# Alignment.net
KiCad netlist of a schematic drawn in EAGLE
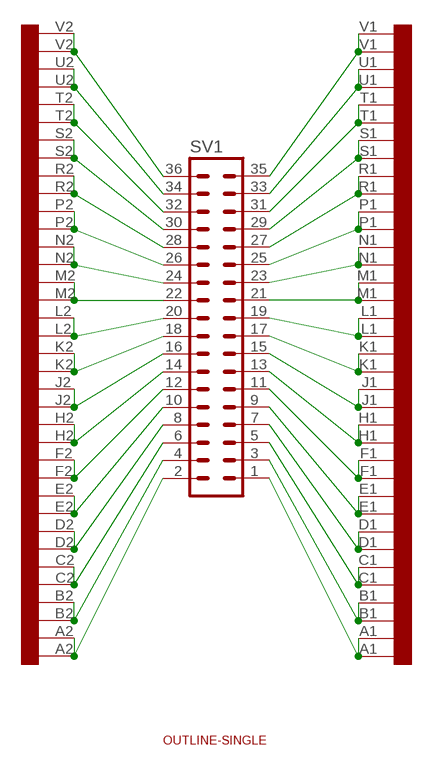
[diagram p0: schematic, sheet 1]

(export (version "E")
  (design (tool "Eeschema 10.0.6"))
  (components
    (comp (ref "EDGE")
      (value "EDGE-2ECONO")
      (footprint "eagle-import:ECONOSINGLE")
      (libsource (lib "eagle-import") (part "EDGE-2ECONO"))
    )
    (comp (ref "SV1")
      (value "MA18-2")
      (footprint "eagle-import:MA18-2")
      (libsource (lib "eagle-import") (part "MA18-2"))
    )
    (comp (ref "U$1")
      (value "EDGE-2CONNECTOR")
      (footprint "eagle-import:EDGE-CON2")
      (libsource (lib "eagle-import") (part "EDGE-2CONNECTOR"))
    )
    (comp (ref "U$3")
      (value "OUTLINE-SINGLE")
      (footprint "eagle-import:SINGLE")
      (libsource (lib "eagle-import") (part "OUTLINE-SINGLE"))
    )
  )
  (nets
    (net (code "1") (name "Net-(EDGEA-1)") (class "Default")
      (node (ref "EDGE") (pin "A1") (pinfunction "1_A1") (pintype "bidirectional"))
      (node (ref "SV1") (pin "1") (pinfunction "1_1") (pintype "passive"))
      (node (ref "U$1") (pin "A1") (pinfunction "1_A1") (pintype "bidirectional"))
    )
    (net (code "2") (name "Net-(EDGEAA-1)") (class "Default")
      (node (ref "EDGE") (pin "R1") (pinfunction "1_R1") (pintype "bidirectional"))
      (node (ref "SV1") (pin "27") (pinfunction "27_27") (pintype "passive"))
      (node (ref "U$1") (pin "R1") (pinfunction "1_R1") (pintype "bidirectional"))
    )
    (net (code "3") (name "Net-(EDGEAB-1)") (class "Default")
      (node (ref "EDGE") (pin "R2") (pinfunction "1_R2") (pintype "bidirectional"))
      (node (ref "SV1") (pin "28") (pinfunction "28_28") (pintype "passive"))
      (node (ref "U$1") (pin "R2") (pinfunction "1_R2") (pintype "bidirectional"))
    )
    (net (code "4") (name "Net-(EDGEAC-1)") (class "Default")
      (node (ref "EDGE") (pin "S1") (pinfunction "1_S1") (pintype "bidirectional"))
      (node (ref "SV1") (pin "29") (pinfunction "29_29") (pintype "passive"))
      (node (ref "U$1") (pin "S1") (pinfunction "1_S1") (pintype "bidirectional"))
    )
    (net (code "5") (name "Net-(EDGEAD-1)") (class "Default")
      (node (ref "EDGE") (pin "S2") (pinfunction "1_S2") (pintype "bidirectional"))
      (node (ref "SV1") (pin "30") (pinfunction "30_30") (pintype "passive"))
      (node (ref "U$1") (pin "S2") (pinfunction "1_S2") (pintype "bidirectional"))
    )
    (net (code "6") (name "Net-(EDGEAE-1)") (class "Default")
      (node (ref "EDGE") (pin "T1") (pinfunction "1_T1") (pintype "bidirectional"))
      (node (ref "SV1") (pin "31") (pinfunction "31_31") (pintype "passive"))
      (node (ref "U$1") (pin "T1") (pinfunction "1_T1") (pintype "bidirectional"))
    )
    (net (code "7") (name "Net-(EDGEAF-1)") (class "Default")
      (node (ref "EDGE") (pin "T2") (pinfunction "1_T2") (pintype "bidirectional"))
      (node (ref "SV1") (pin "32") (pinfunction "32_32") (pintype "passive"))
      (node (ref "U$1") (pin "T2") (pinfunction "1_T2") (pintype "bidirectional"))
    )
    (net (code "8") (name "Net-(EDGEAG-1)") (class "Default")
      (node (ref "EDGE") (pin "U1") (pinfunction "1_U1") (pintype "bidirectional"))
      (node (ref "SV1") (pin "33") (pinfunction "33_33") (pintype "passive"))
      (node (ref "U$1") (pin "U1") (pinfunction "1_U1") (pintype "bidirectional"))
    )
    (net (code "9") (name "Net-(EDGEAH-1)") (class "Default")
      (node (ref "EDGE") (pin "U2") (pinfunction "1_U2") (pintype "bidirectional"))
      (node (ref "SV1") (pin "34") (pinfunction "34_34") (pintype "passive"))
      (node (ref "U$1") (pin "U2") (pinfunction "1_U2") (pintype "bidirectional"))
    )
    (net (code "10") (name "Net-(EDGEAI-1)") (class "Default")
      (node (ref "EDGE") (pin "V1") (pinfunction "1_V1") (pintype "bidirectional"))
      (node (ref "SV1") (pin "35") (pinfunction "35_35") (pintype "passive"))
      (node (ref "U$1") (pin "V1") (pinfunction "1_V1") (pintype "bidirectional"))
    )
    (net (code "11") (name "Net-(EDGEAJ-1)") (class "Default")
      (node (ref "EDGE") (pin "V2") (pinfunction "1_V2") (pintype "bidirectional"))
      (node (ref "SV1") (pin "36") (pinfunction "36_36") (pintype "passive"))
      (node (ref "U$1") (pin "V2") (pinfunction "1_V2") (pintype "bidirectional"))
    )
    (net (code "12") (name "Net-(EDGEB-1)") (class "Default")
      (node (ref "EDGE") (pin "A2") (pinfunction "1_A2") (pintype "bidirectional"))
      (node (ref "SV1") (pin "2") (pinfunction "2_2") (pintype "passive"))
      (node (ref "U$1") (pin "A2") (pinfunction "1_A2") (pintype "bidirectional"))
    )
    (net (code "13") (name "Net-(EDGEC-1)") (class "Default")
      (node (ref "EDGE") (pin "B1") (pinfunction "1_B1") (pintype "bidirectional"))
      (node (ref "SV1") (pin "3") (pinfunction "3_3") (pintype "passive"))
      (node (ref "U$1") (pin "B1") (pinfunction "1_B1") (pintype "bidirectional"))
    )
    (net (code "14") (name "Net-(EDGED-1)") (class "Default")
      (node (ref "EDGE") (pin "B2") (pinfunction "1_B2") (pintype "bidirectional"))
      (node (ref "SV1") (pin "4") (pinfunction "4_4") (pintype "passive"))
      (node (ref "U$1") (pin "B2") (pinfunction "1_B2") (pintype "bidirectional"))
    )
    (net (code "15") (name "Net-(EDGEE-1)") (class "Default")
      (node (ref "EDGE") (pin "C1") (pinfunction "1_C1") (pintype "bidirectional"))
      (node (ref "SV1") (pin "5") (pinfunction "5_5") (pintype "passive"))
      (node (ref "U$1") (pin "C1") (pinfunction "1_C1") (pintype "bidirectional"))
    )
    (net (code "16") (name "Net-(EDGEF-1)") (class "Default")
      (node (ref "EDGE") (pin "C2") (pinfunction "1_C2") (pintype "bidirectional"))
      (node (ref "SV1") (pin "6") (pinfunction "6_6") (pintype "passive"))
      (node (ref "U$1") (pin "C2") (pinfunction "1_C2") (pintype "bidirectional"))
    )
    (net (code "17") (name "Net-(EDGEG-1)") (class "Default")
      (node (ref "EDGE") (pin "D1") (pinfunction "1_D1") (pintype "bidirectional"))
      (node (ref "SV1") (pin "7") (pinfunction "7_7") (pintype "passive"))
      (node (ref "U$1") (pin "D1") (pinfunction "1_D1") (pintype "bidirectional"))
    )
    (net (code "18") (name "Net-(EDGEH-1)") (class "Default")
      (node (ref "EDGE") (pin "D2") (pinfunction "1_D2") (pintype "bidirectional"))
      (node (ref "SV1") (pin "8") (pinfunction "8_8") (pintype "passive"))
      (node (ref "U$1") (pin "D2") (pinfunction "1_D2") (pintype "bidirectional"))
    )
    (net (code "19") (name "Net-(EDGEI-1)") (class "Default")
      (node (ref "EDGE") (pin "E1") (pinfunction "1_E1") (pintype "bidirectional"))
      (node (ref "SV1") (pin "9") (pinfunction "9_9") (pintype "passive"))
      (node (ref "U$1") (pin "E1") (pinfunction "1_E1") (pintype "bidirectional"))
    )
    (net (code "20") (name "Net-(EDGEJ-1)") (class "Default")
      (node (ref "EDGE") (pin "E2") (pinfunction "1_E2") (pintype "bidirectional"))
      (node (ref "SV1") (pin "10") (pinfunction "10_10") (pintype "passive"))
      (node (ref "U$1") (pin "E2") (pinfunction "1_E2") (pintype "bidirectional"))
    )
    (net (code "21") (name "Net-(EDGEK-1)") (class "Default")
      (node (ref "EDGE") (pin "F1") (pinfunction "1_F1") (pintype "bidirectional"))
      (node (ref "SV1") (pin "11") (pinfunction "11_11") (pintype "passive"))
      (node (ref "U$1") (pin "F1") (pinfunction "1_F1") (pintype "bidirectional"))
    )
    (net (code "22") (name "Net-(EDGEL-1)") (class "Default")
      (node (ref "EDGE") (pin "F2") (pinfunction "1_F2") (pintype "bidirectional"))
      (node (ref "SV1") (pin "12") (pinfunction "12_12") (pintype "passive"))
      (node (ref "U$1") (pin "F2") (pinfunction "1_F2") (pintype "bidirectional"))
    )
    (net (code "23") (name "Net-(EDGEM-1)") (class "Default")
      (node (ref "EDGE") (pin "H1") (pinfunction "1_H1") (pintype "bidirectional"))
      (node (ref "SV1") (pin "13") (pinfunction "13_13") (pintype "passive"))
      (node (ref "U$1") (pin "H1") (pinfunction "1_H1") (pintype "bidirectional"))
    )
    (net (code "24") (name "Net-(EDGEN-1)") (class "Default")
      (node (ref "EDGE") (pin "H2") (pinfunction "1_H2") (pintype "bidirectional"))
      (node (ref "SV1") (pin "14") (pinfunction "14_14") (pintype "passive"))
      (node (ref "U$1") (pin "H2") (pinfunction "1_H2") (pintype "bidirectional"))
    )
    (net (code "25") (name "Net-(EDGEO-1)") (class "Default")
      (node (ref "EDGE") (pin "J1") (pinfunction "1_J1") (pintype "bidirectional"))
      (node (ref "SV1") (pin "15") (pinfunction "15_15") (pintype "passive"))
      (node (ref "U$1") (pin "J1") (pinfunction "1_J1") (pintype "bidirectional"))
    )
    (net (code "26") (name "Net-(EDGEP-1)") (class "Default")
      (node (ref "EDGE") (pin "J2") (pinfunction "1_J2") (pintype "bidirectional"))
      (node (ref "SV1") (pin "16") (pinfunction "16_16") (pintype "passive"))
      (node (ref "U$1") (pin "J2") (pinfunction "1_J2") (pintype "bidirectional"))
    )
    (net (code "27") (name "Net-(EDGEQ-1)") (class "Default")
      (node (ref "EDGE") (pin "K1") (pinfunction "1_K1") (pintype "bidirectional"))
      (node (ref "SV1") (pin "17") (pinfunction "17_17") (pintype "passive"))
      (node (ref "U$1") (pin "K1") (pinfunction "1_K1") (pintype "bidirectional"))
    )
    (net (code "28") (name "Net-(EDGER-1)") (class "Default")
      (node (ref "EDGE") (pin "K2") (pinfunction "1_K2") (pintype "bidirectional"))
      (node (ref "SV1") (pin "18") (pinfunction "18_18") (pintype "passive"))
      (node (ref "U$1") (pin "K2") (pinfunction "1_K2") (pintype "bidirectional"))
    )
    (net (code "29") (name "Net-(EDGES-1)") (class "Default")
      (node (ref "EDGE") (pin "L1") (pinfunction "1_L1") (pintype "bidirectional"))
      (node (ref "SV1") (pin "19") (pinfunction "19_19") (pintype "passive"))
      (node (ref "U$1") (pin "L1") (pinfunction "1_L1") (pintype "bidirectional"))
    )
    (net (code "30") (name "Net-(EDGET-1)") (class "Default")
      (node (ref "EDGE") (pin "L2") (pinfunction "1_L2") (pintype "bidirectional"))
      (node (ref "SV1") (pin "20") (pinfunction "20_20") (pintype "passive"))
      (node (ref "U$1") (pin "L2") (pinfunction "1_L2") (pintype "bidirectional"))
    )
    (net (code "31") (name "Net-(EDGEU-1)") (class "Default")
      (node (ref "EDGE") (pin "M1") (pinfunction "1_M1") (pintype "bidirectional"))
      (node (ref "SV1") (pin "21") (pinfunction "21_21") (pintype "passive"))
      (node (ref "U$1") (pin "M1") (pinfunction "1_M1") (pintype "bidirectional"))
    )
    (net (code "32") (name "Net-(EDGEV-1)") (class "Default")
      (node (ref "EDGE") (pin "M2") (pinfunction "1_M2") (pintype "bidirectional"))
      (node (ref "SV1") (pin "22") (pinfunction "22_22") (pintype "passive"))
      (node (ref "U$1") (pin "M2") (pinfunction "1_M2") (pintype "bidirectional"))
    )
    (net (code "33") (name "Net-(EDGEW-1)") (class "Default")
      (node (ref "EDGE") (pin "N1") (pinfunction "1_N1") (pintype "bidirectional"))
      (node (ref "SV1") (pin "23") (pinfunction "23_23") (pintype "passive"))
      (node (ref "U$1") (pin "N1") (pinfunction "1_N1") (pintype "bidirectional"))
    )
    (net (code "34") (name "Net-(EDGEX-1)") (class "Default")
      (node (ref "EDGE") (pin "N2") (pinfunction "1_N2") (pintype "bidirectional"))
      (node (ref "SV1") (pin "24") (pinfunction "24_24") (pintype "passive"))
      (node (ref "U$1") (pin "N2") (pinfunction "1_N2") (pintype "bidirectional"))
    )
    (net (code "35") (name "Net-(EDGEY-1)") (class "Default")
      (node (ref "EDGE") (pin "P1") (pinfunction "1_P1") (pintype "bidirectional"))
      (node (ref "SV1") (pin "25") (pinfunction "25_25") (pintype "passive"))
      (node (ref "U$1") (pin "P1") (pinfunction "1_P1") (pintype "bidirectional"))
    )
    (net (code "36") (name "Net-(EDGEZ-1)") (class "Default")
      (node (ref "EDGE") (pin "P2") (pinfunction "1_P2") (pintype "bidirectional"))
      (node (ref "SV1") (pin "26") (pinfunction "26_26") (pintype "passive"))
      (node (ref "U$1") (pin "P2") (pinfunction "1_P2") (pintype "bidirectional"))
    )
  )
)
